# DriverBoard.net
KiCad netlist of a schematic drawn in EAGLE
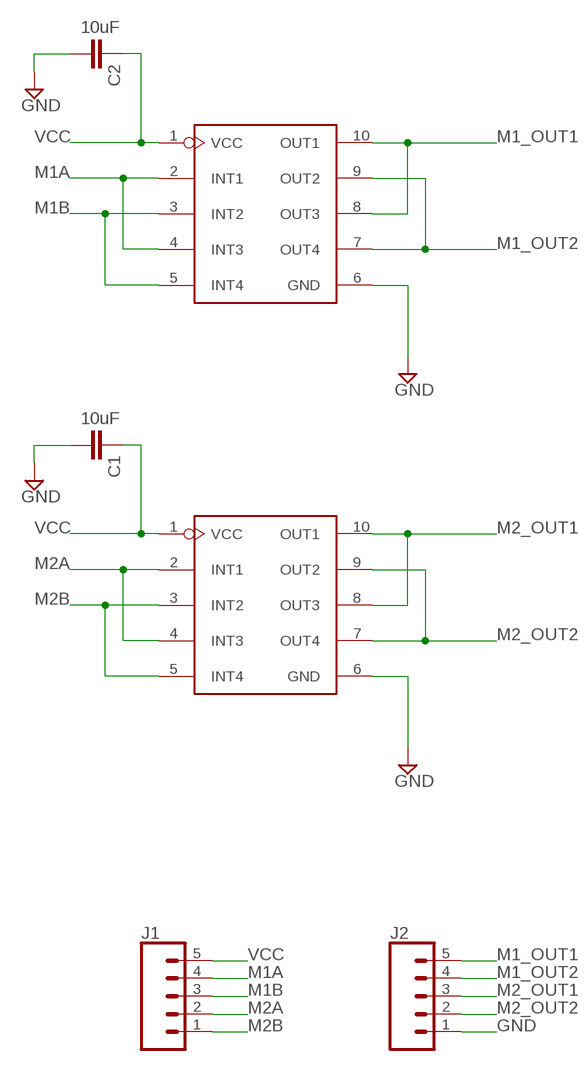
[diagram p0: schematic, sheet 1]

(export (version "E")
  (design (tool "Eeschema 10.0.6"))
  (components
    (comp (ref "C1")
      (value "10uF")
      (footprint "eagle-import:C0805")
      (libsource (lib "eagle-import") (part "C-EUC0805"))
    )
    (comp (ref "C2")
      (value "10uF")
      (footprint "eagle-import:C0805")
      (libsource (lib "eagle-import") (part "C-EUC0805"))
    )
    (comp (ref "J1")
      (value "CONN_05")
      (footprint "eagle-import:1X05")
      (libsource (lib "eagle-import") (part "CONN_05"))
    )
    (comp (ref "J2")
      (value "CONN_05")
      (footprint "eagle-import:1X05")
      (libsource (lib "eagle-import") (part "CONN_05"))
    )
    (comp (ref "U1")
      (value "DRIVER-LV8548MC-AH(SOIC10)")
      (footprint "eagle-import:SOIC10-1.0-5X4MM")
      (fields (field (name "MF") "ON Semiconductor") (field (name "MP") "LV8548MC-AH"))
      (libsource (lib "eagle-import") (part "DRIVER-LV8548MC-AH(SOIC10)"))
    )
    (comp (ref "U2")
      (value "DRIVER-LV8548MC-AH(SOIC10)")
      (footprint "eagle-import:SOIC10-1.0-5X4MM")
      (fields (field (name "MF") "ON Semiconductor") (field (name "MP") "LV8548MC-AH"))
      (libsource (lib "eagle-import") (part "DRIVER-LV8548MC-AH(SOIC10)"))
    )
  )
  (nets
    (net (code "1") (name "/M1A") (class "Default")
      (node (ref "J1") (pin "4") (pinfunction "4_4") (pintype "passive"))
      (node (ref "U2") (pin "2") (pinfunction "INT1_2") (pintype "bidirectional"))
      (node (ref "U2") (pin "4") (pinfunction "INT3_4") (pintype "bidirectional"))
    )
    (net (code "2") (name "/M1B") (class "Default")
      (node (ref "J1") (pin "3") (pinfunction "3_3") (pintype "passive"))
      (node (ref "U2") (pin "3") (pinfunction "INT2_3") (pintype "bidirectional"))
      (node (ref "U2") (pin "5") (pinfunction "INT4_5") (pintype "bidirectional"))
    )
    (net (code "3") (name "/M1_OUT1") (class "Default")
      (node (ref "J2") (pin "5") (pinfunction "5_5") (pintype "passive"))
      (node (ref "U2") (pin "10") (pinfunction "OUT1_10") (pintype "bidirectional"))
      (node (ref "U2") (pin "8") (pinfunction "OUT3_8") (pintype "bidirectional"))
    )
    (net (code "4") (name "/M1_OUT2") (class "Default")
      (node (ref "J2") (pin "4") (pinfunction "4_4") (pintype "passive"))
      (node (ref "U2") (pin "7") (pinfunction "OUT4_7") (pintype "bidirectional"))
      (node (ref "U2") (pin "9") (pinfunction "OUT2_9") (pintype "bidirectional"))
    )
    (net (code "5") (name "/M2A") (class "Default")
      (node (ref "J1") (pin "2") (pinfunction "2_2") (pintype "passive"))
      (node (ref "U1") (pin "2") (pinfunction "INT1_2") (pintype "bidirectional"))
      (node (ref "U1") (pin "4") (pinfunction "INT3_4") (pintype "bidirectional"))
    )
    (net (code "6") (name "/M2B") (class "Default")
      (node (ref "J1") (pin "1") (pinfunction "1_1") (pintype "passive"))
      (node (ref "U1") (pin "3") (pinfunction "INT2_3") (pintype "bidirectional"))
      (node (ref "U1") (pin "5") (pinfunction "INT4_5") (pintype "bidirectional"))
    )
    (net (code "7") (name "/M2_OUT1") (class "Default")
      (node (ref "J2") (pin "3") (pinfunction "3_3") (pintype "passive"))
      (node (ref "U1") (pin "10") (pinfunction "OUT1_10") (pintype "bidirectional"))
      (node (ref "U1") (pin "8") (pinfunction "OUT3_8") (pintype "bidirectional"))
    )
    (net (code "8") (name "/M2_OUT2") (class "Default")
      (node (ref "J2") (pin "2") (pinfunction "2_2") (pintype "passive"))
      (node (ref "U1") (pin "7") (pinfunction "OUT4_7") (pintype "bidirectional"))
      (node (ref "U1") (pin "9") (pinfunction "OUT2_9") (pintype "bidirectional"))
    )
    (net (code "9") (name "/VCC") (class "Default")
      (node (ref "C1") (pin "1") (pinfunction "1_1") (pintype "passive"))
      (node (ref "C2") (pin "1") (pinfunction "1_1") (pintype "passive"))
      (node (ref "J1") (pin "5") (pinfunction "5_5") (pintype "passive"))
      (node (ref "U1") (pin "1") (pinfunction "VCC_1") (pintype "bidirectional"))
      (node (ref "U2") (pin "1") (pinfunction "VCC_1") (pintype "bidirectional"))
    )
    (net (code "10") (name "GND") (class "Default")
      (node (ref "C1") (pin "2") (pinfunction "2_2") (pintype "passive"))
      (node (ref "C2") (pin "2") (pinfunction "2_2") (pintype "passive"))
      (node (ref "J2") (pin "1") (pinfunction "1_1") (pintype "passive"))
      (node (ref "U1") (pin "6") (pinfunction "GND_6") (pintype "bidirectional"))
      (node (ref "U2") (pin "6") (pinfunction "GND_6") (pintype "bidirectional"))
    )
  )
)
